# transmitter.net
KiCad netlist of a schematic drawn in Altium Designer
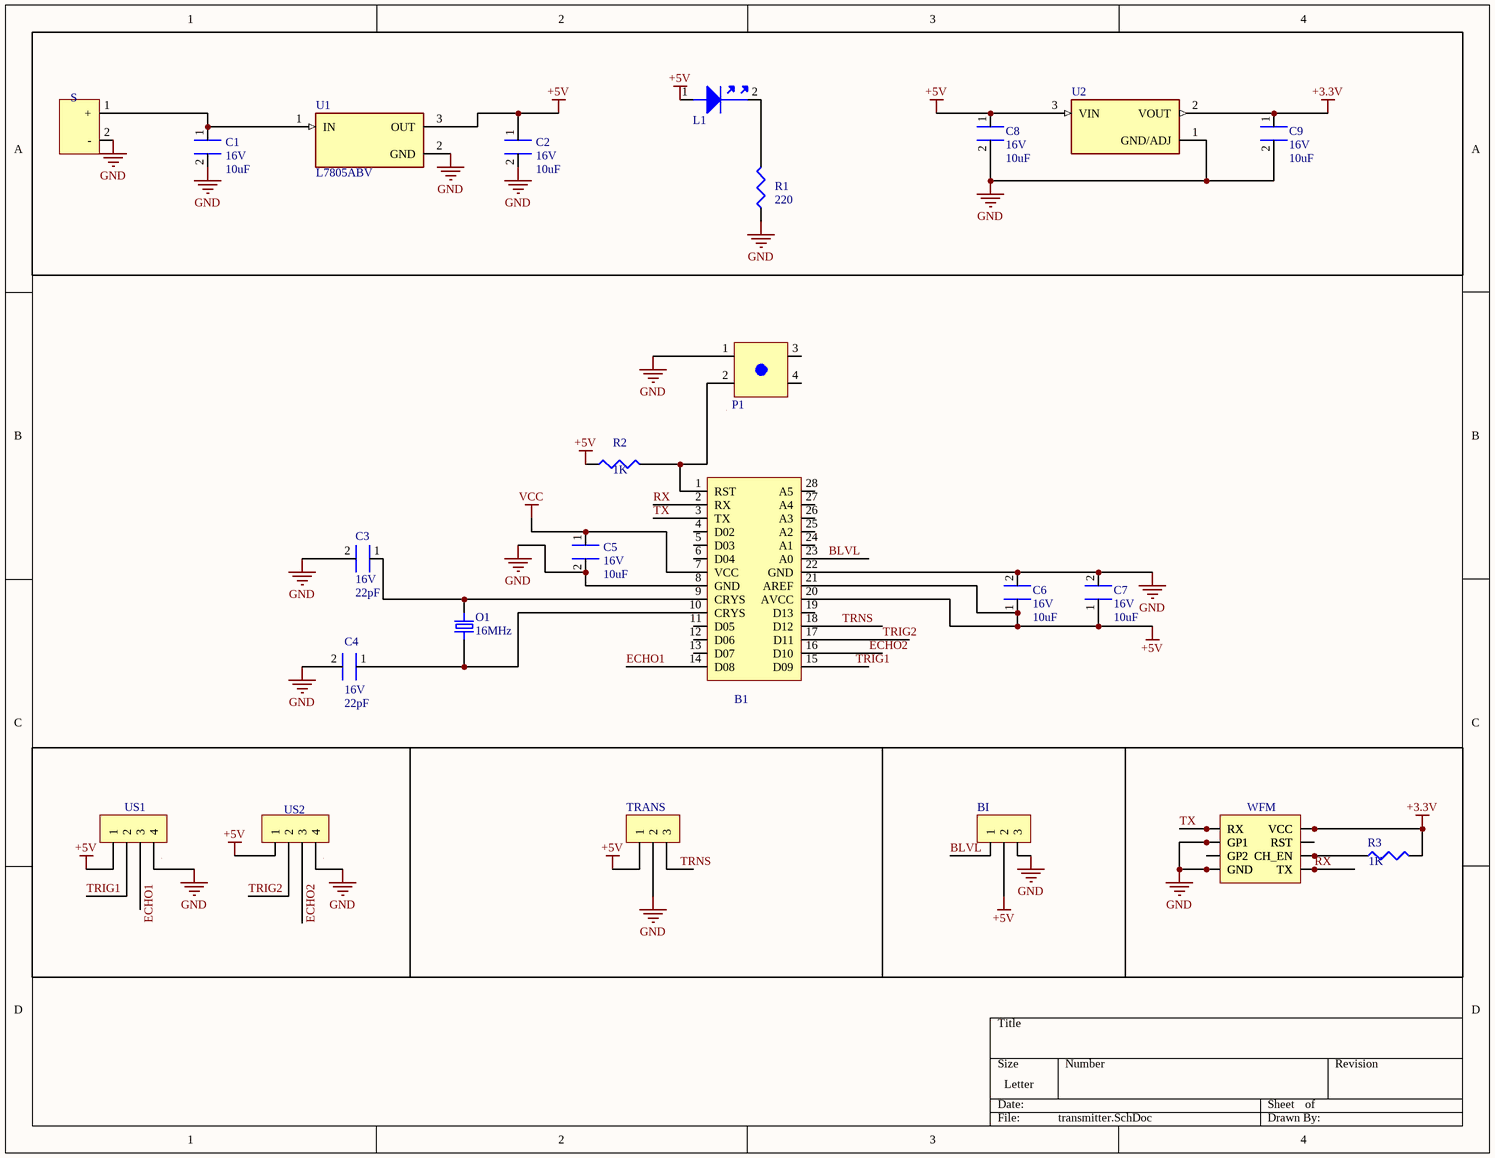
[diagram p0: transmitter.SchDoc]

(export (version "E")
  (design (tool "Eeschema 10.0.6"))
  (components
    (comp (ref "B1")
      (value "1-2199298-8")
      (footprint "FP-1-2199298-9-MFG")
      (description "IC Socket")
      (fields (field (name "MANUFACTURER") "TE Connectivity"))
      (libsource (lib "transmitter") (part "1-2199298-8"))
    )
    (comp (ref "BI")
      (value "5-535541-1")
      (footprint "Female")
      (fields (field (name "MANUFACTURER") "TE Connectivity"))
      (libsource (lib "transmitter") (part "5-535541-1"))
    )
    (comp (ref "C1")
      (value "EEA-GA1C100")
      (footprint "10uF_Capacitor - duplicate")
      (fields
        (field (name "MANUFACTURER") "Panasonic")
        (field (name "VOLTAGE") "16V")
        (field (name "CAPACITANCE") "10uF")
      )
      (libsource (lib "transmitter") (part "EEA-GA1C100"))
    )
    (comp (ref "C2")
      (value "EEA-GA1C100")
      (footprint "10uF_Capacitor - duplicate")
      (fields
        (field (name "MANUFACTURER") "Panasonic")
        (field (name "VOLTAGE") "16V")
        (field (name "CAPACITANCE") "10uF")
      )
      (libsource (lib "transmitter") (part "EEA-GA1C100"))
    )
    (comp (ref "C3")
      (value "S220K25SL0N63L6R")
      (footprint "10uF_Capacitor - duplicate")
      (fields
        (field (name "MANUFACTURER") "Vishay BCcomponents")
        (field (name "VOLTAGE") "16V")
        (field (name "CAPACITANCE") "22pF")
      )
      (libsource (lib "transmitter") (part "S220K25SL0N63L6R"))
    )
    (comp (ref "C4")
      (value "S220K25SL0N63L6R")
      (footprint "10uF_Capacitor - duplicate")
      (fields
        (field (name "MANUFACTURER") "Vishay BCcomponents")
        (field (name "VOLTAGE") "16V")
        (field (name "CAPACITANCE") "22pF")
      )
      (libsource (lib "transmitter") (part "S220K25SL0N63L6R"))
    )
    (comp (ref "C5")
      (value "EEA-GA1C100")
      (footprint "10uF_Capacitor - duplicate")
      (fields
        (field (name "MANUFACTURER") "Panasonic")
        (field (name "VOLTAGE") "16V")
        (field (name "CAPACITANCE") "10uF")
      )
      (libsource (lib "transmitter") (part "EEA-GA1C100"))
    )
    (comp (ref "C6")
      (value "EEA-GA1C100")
      (footprint "10uF_Capacitor - duplicate")
      (fields
        (field (name "MANUFACTURER") "Panasonic")
        (field (name "VOLTAGE") "16V")
        (field (name "CAPACITANCE") "10uF")
      )
      (libsource (lib "transmitter") (part "EEA-GA1C100"))
    )
    (comp (ref "C7")
      (value "EEA-GA1C100")
      (footprint "10uF_Capacitor - duplicate")
      (fields
        (field (name "MANUFACTURER") "Panasonic")
        (field (name "VOLTAGE") "16V")
        (field (name "CAPACITANCE") "10uF")
      )
      (libsource (lib "transmitter") (part "EEA-GA1C100"))
    )
    (comp (ref "C8")
      (value "EEA-GA1C100")
      (footprint "10uF_Capacitor - duplicate")
      (fields
        (field (name "MANUFACTURER") "Panasonic")
        (field (name "VOLTAGE") "16V")
        (field (name "CAPACITANCE") "10uF")
      )
      (libsource (lib "transmitter") (part "EEA-GA1C100"))
    )
    (comp (ref "C9")
      (value "EEA-GA1C100")
      (footprint "10uF_Capacitor - duplicate")
      (fields
        (field (name "MANUFACTURER") "Panasonic")
        (field (name "VOLTAGE") "16V")
        (field (name "CAPACITANCE") "10uF")
      )
      (libsource (lib "transmitter") (part "EEA-GA1C100"))
    )
    (comp (ref "L1")
      (value "WP7113SRD/J4")
      (footprint "LEDRD254W57D500H1070")
      (description "LED Uni-Color SB. Red 660nm 2-Pin T-1 3/4 Bulk")
      (fields (field (name "MANUFACTURER") "Kingbright"))
      (libsource (lib "transmitter") (part "WP7113SRD/J4"))
    )
    (comp (ref "O1")
      (value "16MHz")
      (footprint "Oscillator")
      (fields (field (name "MP") "ECS-160-20-4") (field (name "Comment") "ECS-160-20-4_1"))
      (libsource (lib "transmitter") (part "ECS-160-20-4_1"))
    )
    (comp (ref "P1")
      (value "COM-00097")
      (footprint "P_button")
      (description "CONN HEADER SMD 28POS 0.8MM")
      (fields (field (name "MANUFACTURER") "SparkFun"))
      (libsource (lib "transmitter") (part "COM-00097"))
    )
    (comp (ref "R1")
      (value "CFM12JT220R")
      (footprint "Resister")
      (description "Fixed Resistor, Carbon Film, 0.5W, 220ohm, 350V, 5% +/-Tol, -400,0ppm/Cel, Through Hole Mount")
      (fields
        (field (name "MANUFACTURER") "Stackpole Electronics")
        (field (name "POWER") "500mW")
        (field (name "RESISTANCE") "220")
      )
      (libsource (lib "transmitter") (part "CFM12JT220R"))
    )
    (comp (ref "R2")
      (value "CFM12JT1K00")
      (footprint "Resister")
      (description "Fixed Resistor, Carbon Film, 0.5W, 1000ohm, 350V, 5% +/-Tol, -400,0ppm/Cel, Through Hole Mount")
      (fields
        (field (name "MANUFACTURER") "Stackpole Electronics")
        (field (name "POWER") "500mW")
        (field (name "RESISTANCE") "1K")
      )
      (libsource (lib "transmitter") (part "CFM12JT1K00"))
    )
    (comp (ref "R3")
      (value "CFM12JT1K00")
      (footprint "Resister")
      (description "Fixed Resistor, Carbon Film, 0.5W, 1000ohm, 350V, 5% +/-Tol, -400,0ppm/Cel, Through Hole Mount")
      (fields
        (field (name "MANUFACTURER") "Stackpole Electronics")
        (field (name "POWER") "500mW")
        (field (name "RESISTANCE") "1K")
      )
      (libsource (lib "transmitter") (part "CFM12JT1K00"))
    )
    (comp (ref "S")
      (value "TB006-508-02BE")
      (footprint "terminalbox")
      (description "Barrier Strip Terminal Block")
      (fields (field (name "MANUFACTURER") "CUI Devices"))
      (libsource (lib "transmitter") (part "TB006-508-02BE"))
    )
    (comp (ref "TRANS")
      (value "5-535541-1")
      (footprint "Female")
      (fields (field (name "MANUFACTURER") "TE Connectivity"))
      (libsource (lib "transmitter") (part "5-535541-1"))
    )
    (comp (ref "U1")
      (value "L7805ABV")
      (footprint "TO220")
      (description "Linear Voltage Regulator IC 1 Output 1.5A TO-220AB")
      (fields (field (name "MF") "STMicroelectronics"))
      (libsource (lib "transmitter") (part "L7805ABV"))
    )
    (comp (ref "U2")
      (value "AMS1117-3.3")
      (footprint "SOT229P700X180-4N")
      (description "Sot223/Pkg 1-Amp 3.3-Volt Low Drop Out Voltage Regulatator")
      (fields (field (name "MF") "Advanced Monolithic Systems"))
      (libsource (lib "AMS1117-3.3") (part "AMS1117-3.3"))
    )
    (comp (ref "US1")
      (value "61300411121")
      (footprint "61300411121")
      (fields (field (name "MANUFACTURER") "Wurth Electronics"))
      (libsource (lib "transmitter") (part "61300411121"))
    )
    (comp (ref "US2")
      (value "61300411121")
      (footprint "61300411121")
      (fields (field (name "MANUFACTURER") "Wurth Electronics"))
      (libsource (lib "transmitter") (part "61300411121"))
    )
    (comp (ref "WFM")
      (value "PPPC042LFBN-RC")
      (footprint "SULLINS_PPPC042LFBN-RC")
      (description "Female, 8 C, Straight, .100\"CC; 3.20mm Tail, No Mounting; PBT, Phos. Bronze, 105 C")
      (fields (field (name "MANUFACTURER") "Sullins"))
      (libsource (lib "transmitter") (part "PPPC042LFBN-RC"))
    )
  )
  (nets
    (net (code "1") (name "+3.3V") (class "Default")
      (node (ref "C9") (pin "1") (pinfunction "+_1") (pintype "passive"))
      (node (ref "R3") (pin "2") (pinfunction "2_2") (pintype "passive"))
      (node (ref "U2") (pin "2") (pinfunction "VOUT_2") (pintype "output"))
      (node (ref "WFM") (pin "1") (pinfunction "VCC_1") (pintype "passive"))
    )
    (net (code "2") (name "+5V") (class "Default")
      (node (ref "B1") (pin "20") (pinfunction "AVCC_20") (pintype "power_in"))
      (node (ref "B1") (pin "21") (pinfunction "AREF_21") (pintype "passive"))
      (node (ref "BI") (pin "2") (pinfunction "2_2") (pintype "passive"))
      (node (ref "C2") (pin "1") (pinfunction "+_1") (pintype "passive"))
      (node (ref "C6") (pin "1") (pinfunction "+_1") (pintype "passive"))
      (node (ref "C7") (pin "1") (pinfunction "+_1") (pintype "passive"))
      (node (ref "C8") (pin "1") (pinfunction "+_1") (pintype "passive"))
      (node (ref "L1") (pin "1") (pinfunction "A_1") (pintype "passive"))
      (node (ref "R2") (pin "1") (pinfunction "1_1") (pintype "passive"))
      (node (ref "TRANS") (pin "1") (pinfunction "1_1") (pintype "passive"))
      (node (ref "U1") (pin "3") (pinfunction "OUT_3") (pintype "power_in"))
      (node (ref "U2") (pin "3") (pinfunction "VIN_3") (pintype "input"))
      (node (ref "US1") (pin "1") (pinfunction "1_1") (pintype "passive"))
      (node (ref "US2") (pin "1") (pinfunction "1_1") (pintype "passive"))
    )
    (net (code "3") (name "/BLVL") (class "Default")
      (node (ref "B1") (pin "23") (pinfunction "A0_23") (pintype "passive"))
      (node (ref "BI") (pin "1") (pinfunction "1_1") (pintype "passive"))
    )
    (net (code "4") (name "/ECHO1") (class "Default")
      (node (ref "B1") (pin "14") (pinfunction "D08_14") (pintype "bidirectional"))
      (node (ref "US1") (pin "3") (pinfunction "3_3") (pintype "passive"))
    )
    (net (code "5") (name "/ECHO2") (class "Default")
      (node (ref "B1") (pin "16") (pinfunction "D10_16") (pintype "bidirectional"))
      (node (ref "US2") (pin "3") (pinfunction "3_3") (pintype "passive"))
    )
    (net (code "6") (name "/RX") (class "Default")
      (node (ref "B1") (pin "2") (pinfunction "RX_2") (pintype "bidirectional"))
      (node (ref "WFM") (pin "7") (pinfunction "TX_7") (pintype "passive"))
    )
    (net (code "7") (name "/TRIG1") (class "Default")
      (node (ref "B1") (pin "15") (pinfunction "D09_15") (pintype "bidirectional"))
      (node (ref "US1") (pin "2") (pinfunction "2_2") (pintype "passive"))
    )
    (net (code "8") (name "/TRIG2") (class "Default")
      (node (ref "B1") (pin "17") (pinfunction "D11_17") (pintype "bidirectional"))
      (node (ref "US2") (pin "2") (pinfunction "2_2") (pintype "passive"))
    )
    (net (code "9") (name "/TRNS") (class "Default")
      (node (ref "B1") (pin "18") (pinfunction "D12_18") (pintype "bidirectional"))
      (node (ref "TRANS") (pin "3") (pinfunction "3_3") (pintype "passive"))
    )
    (net (code "10") (name "/TX") (class "Default")
      (node (ref "B1") (pin "3") (pinfunction "TX_3") (pintype "bidirectional"))
      (node (ref "WFM") (pin "2") (pinfunction "RX_2") (pintype "passive"))
    )
    (net (code "11") (name "GND") (class "Default")
      (node (ref "B1") (pin "22") (pinfunction "GND_22") (pintype "power_in"))
      (node (ref "B1") (pin "8") (pinfunction "GND_8") (pintype "power_in"))
      (node (ref "BI") (pin "3") (pinfunction "3_3") (pintype "passive"))
      (node (ref "C1") (pin "2") (pinfunction "-_2") (pintype "passive"))
      (node (ref "C2") (pin "2") (pinfunction "-_2") (pintype "passive"))
      (node (ref "C3") (pin "2") (pinfunction "2_2") (pintype "passive"))
      (node (ref "C4") (pin "2") (pinfunction "2_2") (pintype "passive"))
      (node (ref "C5") (pin "2") (pinfunction "-_2") (pintype "passive"))
      (node (ref "C6") (pin "2") (pinfunction "-_2") (pintype "passive"))
      (node (ref "C7") (pin "2") (pinfunction "-_2") (pintype "passive"))
      (node (ref "C8") (pin "2") (pinfunction "-_2") (pintype "passive"))
      (node (ref "C9") (pin "2") (pinfunction "-_2") (pintype "passive"))
      (node (ref "P1") (pin "1") (pinfunction "4_1") (pintype "passive"))
      (node (ref "R1") (pin "1") (pinfunction "1_1") (pintype "passive"))
      (node (ref "S") (pin "2") (pinfunction "-_2") (pintype "power_in"))
      (node (ref "TRANS") (pin "2") (pinfunction "2_2") (pintype "passive"))
      (node (ref "U1") (pin "2") (pinfunction "GND_2") (pintype "power_in"))
      (node (ref "U2") (pin "1") (pinfunction "GND/ADJ_1") (pintype "power_in"))
      (node (ref "US1") (pin "4") (pinfunction "4_4") (pintype "passive"))
      (node (ref "US2") (pin "4") (pinfunction "4_4") (pintype "passive"))
      (node (ref "WFM") (pin "4") (pinfunction "GP1_4") (pintype "passive"))
      (node (ref "WFM") (pin "8") (pinfunction "GND_8") (pintype "passive"))
    )
    (net (code "12") (name "Net-(B1-CRYS-Pad9)") (class "Default")
      (node (ref "B1") (pin "9") (pinfunction "CRYS_9") (pintype "passive"))
      (node (ref "C3") (pin "1") (pinfunction "1_1") (pintype "passive"))
      (node (ref "O1") (pin "2") (pinfunction "2_2") (pintype "passive"))
    )
    (net (code "13") (name "Net-(B1-CRYS-Pad10)") (class "Default")
      (node (ref "B1") (pin "10") (pinfunction "CRYS_10") (pintype "passive"))
      (node (ref "C4") (pin "1") (pinfunction "1_1") (pintype "passive"))
      (node (ref "O1") (pin "1") (pinfunction "1_1") (pintype "passive"))
    )
    (net (code "14") (name "Net-(B1-RST)") (class "Default")
      (node (ref "B1") (pin "1") (pinfunction "RST_1") (pintype "passive"))
      (node (ref "P1") (pin "2") (pinfunction "3_2") (pintype "passive"))
      (node (ref "R2") (pin "2") (pinfunction "2_2") (pintype "passive"))
    )
    (net (code "15") (name "Net-(C1-+)") (class "Default")
      (node (ref "C1") (pin "1") (pinfunction "+_1") (pintype "passive"))
      (node (ref "S") (pin "1") (pinfunction "+_1") (pintype "power_in"))
      (node (ref "U1") (pin "1") (pinfunction "IN_1") (pintype "input"))
    )
    (net (code "16") (name "Net-(L1-C)") (class "Default")
      (node (ref "L1") (pin "2") (pinfunction "C_2") (pintype "passive"))
      (node (ref "R1") (pin "2") (pinfunction "2_2") (pintype "passive"))
    )
    (net (code "17") (name "Net-(WFM-CH_EN)") (class "Default")
      (node (ref "R3") (pin "1") (pinfunction "1_1") (pintype "passive"))
      (node (ref "WFM") (pin "5") (pinfunction "CH_EN_5") (pintype "passive"))
    )
    (net (code "18") (name "Net-(WFM-GP2)") (class "Default")
      (node (ref "WFM") (pin "6") (pinfunction "GP2_6") (pintype "passive"))
    )
    (net (code "19") (name "Net-(WFM-RST)") (class "Default")
      (node (ref "WFM") (pin "3") (pinfunction "RST_3") (pintype "passive"))
    )
    (net (code "20") (name "VCC") (class "Default")
      (node (ref "B1") (pin "7") (pinfunction "VCC_7") (pintype "power_in"))
      (node (ref "C5") (pin "1") (pinfunction "+_1") (pintype "passive"))
    )
    (net (code "21") (name "unconnected-(B1-A1-Pad24)") (class "Default")
      (node (ref "B1") (pin "24") (pinfunction "A1_24") (pintype "passive"))
    )
    (net (code "22") (name "unconnected-(B1-A2-Pad25)") (class "Default")
      (node (ref "B1") (pin "25") (pinfunction "A2_25") (pintype "passive"))
    )
    (net (code "23") (name "unconnected-(B1-A3-Pad26)") (class "Default")
      (node (ref "B1") (pin "26") (pinfunction "A3_26") (pintype "passive"))
    )
    (net (code "24") (name "unconnected-(B1-A4-Pad27)") (class "Default")
      (node (ref "B1") (pin "27") (pinfunction "A4_27") (pintype "passive"))
    )
    (net (code "25") (name "unconnected-(B1-A5-Pad28)") (class "Default")
      (node (ref "B1") (pin "28") (pinfunction "A5_28") (pintype "passive"))
    )
    (net (code "26") (name "unconnected-(B1-D02-Pad4)") (class "Default")
      (node (ref "B1") (pin "4") (pinfunction "D02_4") (pintype "bidirectional"))
    )
    (net (code "27") (name "unconnected-(B1-D03-Pad5)") (class "Default")
      (node (ref "B1") (pin "5") (pinfunction "D03_5") (pintype "bidirectional"))
    )
    (net (code "28") (name "unconnected-(B1-D04-Pad6)") (class "Default")
      (node (ref "B1") (pin "6") (pinfunction "D04_6") (pintype "bidirectional"))
    )
    (net (code "29") (name "unconnected-(B1-D05-Pad11)") (class "Default")
      (node (ref "B1") (pin "11") (pinfunction "D05_11") (pintype "bidirectional"))
    )
    (net (code "30") (name "unconnected-(B1-D06-Pad12)") (class "Default")
      (node (ref "B1") (pin "12") (pinfunction "D06_12") (pintype "bidirectional"))
    )
    (net (code "31") (name "unconnected-(B1-D07-Pad13)") (class "Default")
      (node (ref "B1") (pin "13") (pinfunction "D07_13") (pintype "bidirectional"))
    )
    (net (code "32") (name "unconnected-(B1-D13-Pad19)") (class "Default")
      (node (ref "B1") (pin "19") (pinfunction "D13_19") (pintype "bidirectional"))
    )
    (net (code "33") (name "unconnected-(P1-1-Pad3)") (class "Default")
      (node (ref "P1") (pin "3") (pinfunction "1_3") (pintype "passive"))
    )
    (net (code "34") (name "unconnected-(P1-2-Pad4)") (class "Default")
      (node (ref "P1") (pin "4") (pinfunction "2_4") (pintype "passive"))
    )
  )
)
